# swarm_circuit.net
KiCad netlist of a schematic drawn in EAGLE
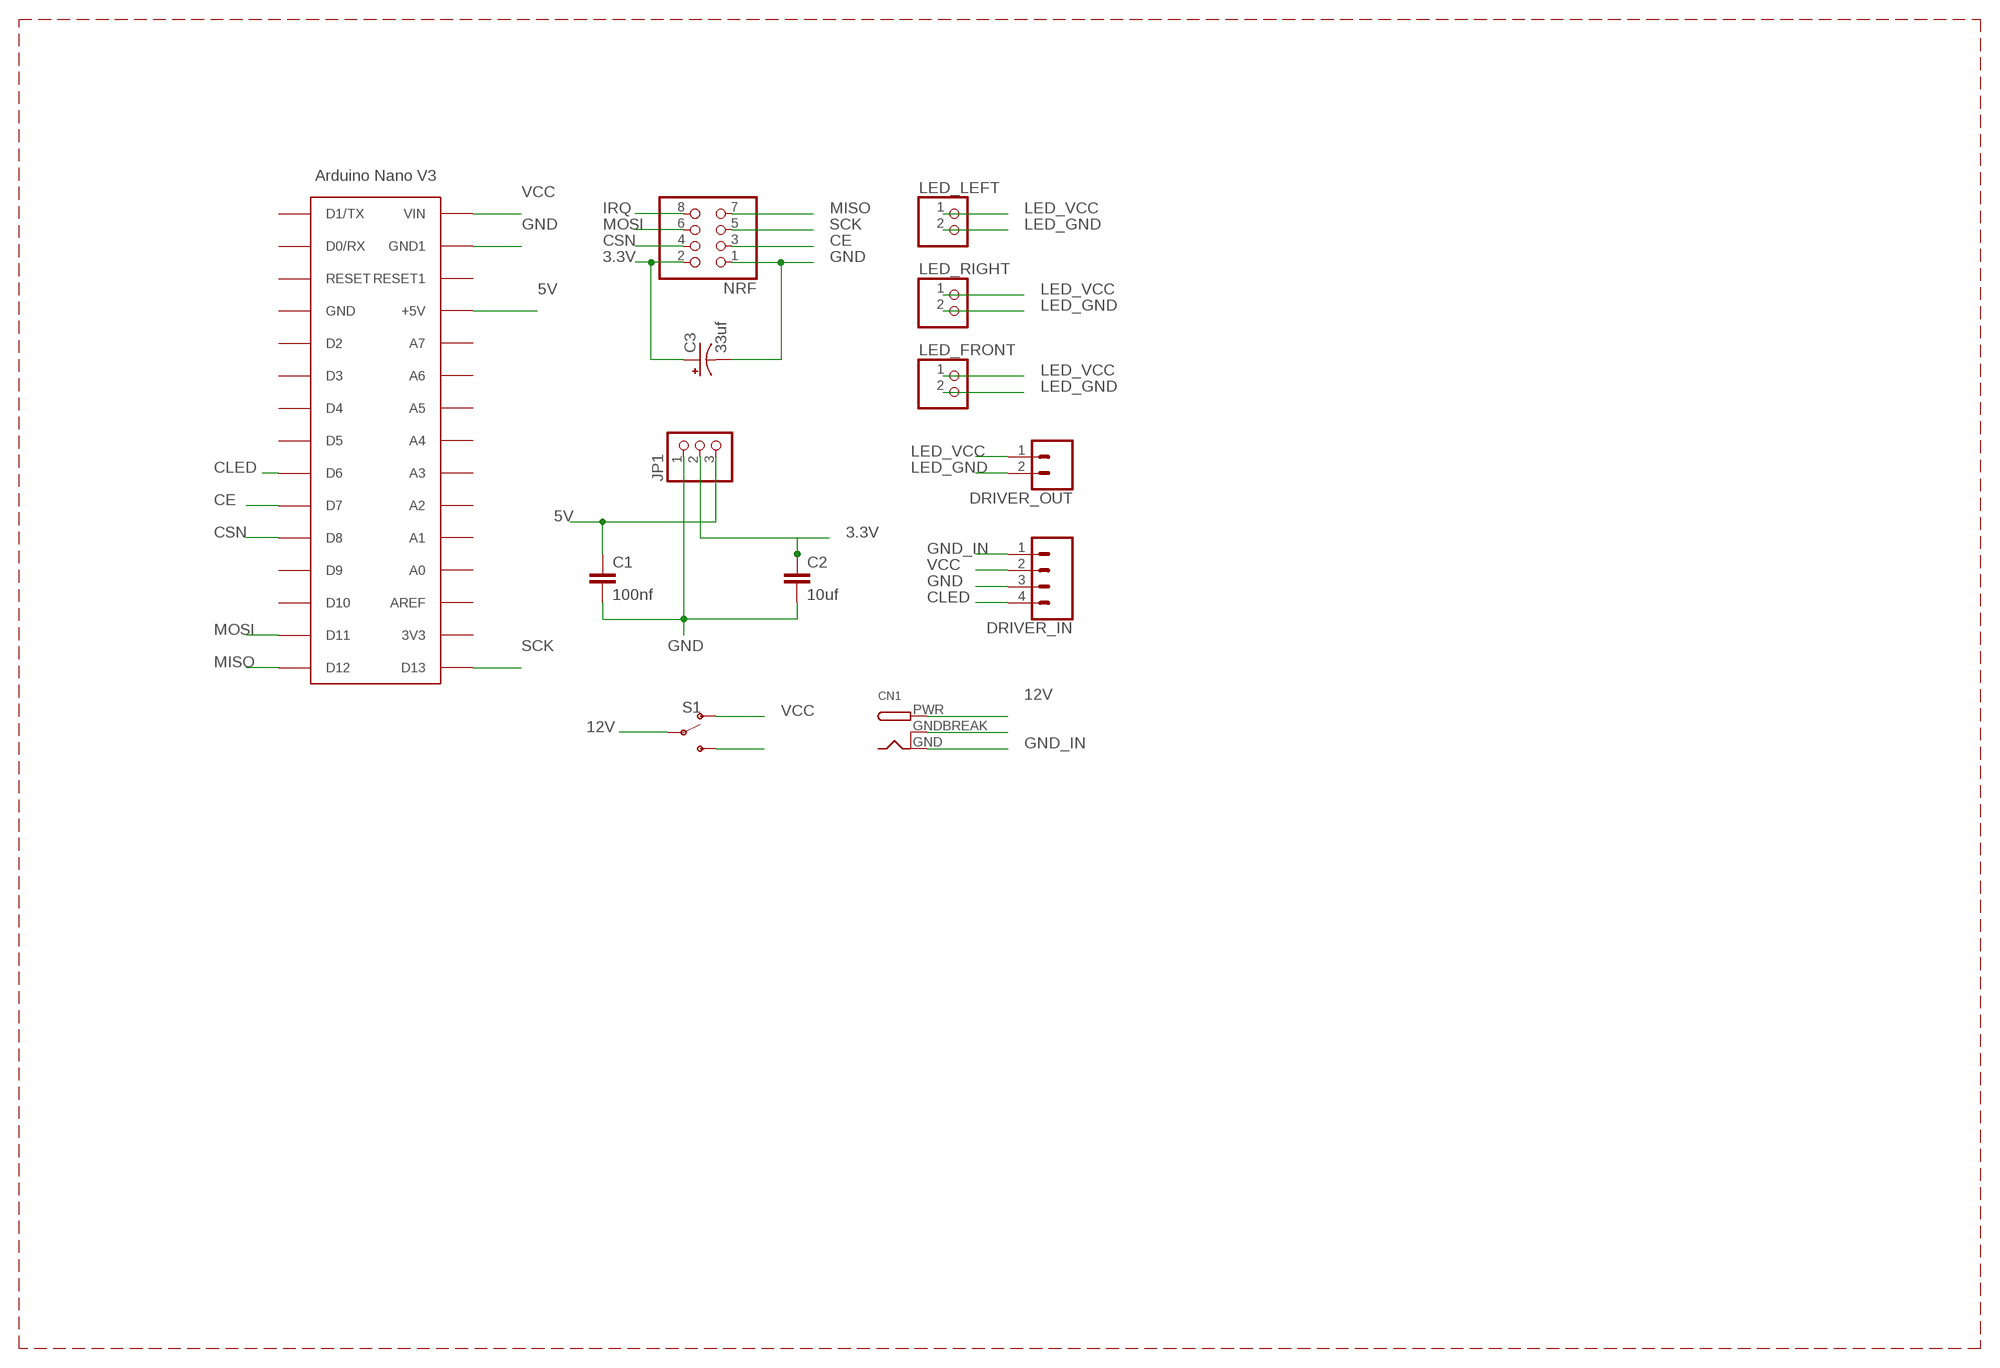
[diagram p0: schematic, sheet 1]

(export (version "E")
  (design (tool "Eeschema 10.0.6"))
  (components
    (comp (ref "C1")
      (value "100nf")
      (footprint "eagle-import:CAP-PTH-SMALL-KIT")
      (libsource (lib "eagle-import") (part "0.1UF-KIT-EZ-50V-20%"))
    )
    (comp (ref "C2")
      (value "10uf")
      (footprint "eagle-import:CAP-PTH-SMALL-KIT")
      (libsource (lib "eagle-import") (part "0.1UF-KIT-EZ-50V-20%"))
    )
    (comp (ref "C3")
      (value "33uf")
      (footprint "eagle-import:CPOL-RADIAL-5MM-10MM-KIT")
      (libsource (lib "eagle-import") (part "1000UF-RADIAL-5MM-35V-20%-KIT"))
    )
    (comp (ref "CN1")
      (value "DCBARRELPTH")
      (footprint "eagle-import:DCJACK_2MM_PTH")
      (libsource (lib "eagle-import") (part "DCBARRELPTH"))
    )
    (comp (ref "DRIVER_IN")
      (value "CONN_04")
      (footprint "eagle-import:1X04")
      (libsource (lib "eagle-import") (part "CONN_04"))
    )
    (comp (ref "DRIVER_OUT")
      (value "CONN_02")
      (footprint "eagle-import:1X02")
      (libsource (lib "eagle-import") (part "CONN_02"))
    )
    (comp (ref "JP1")
      (value "PINHD-1X3")
      (footprint "eagle-import:1X03")
      (libsource (lib "eagle-import") (part "PINHD-1X3"))
    )
    (comp (ref "LED_FRONT")
      (value "HEADER-1X2ROUND")
      (footprint "eagle-import:1X02_ROUND")
      (libsource (lib "eagle-import") (part "HEADER-1X2ROUND"))
    )
    (comp (ref "LED_LEFT")
      (value "HEADER-1X2ROUND")
      (footprint "eagle-import:1X02_ROUND")
      (libsource (lib "eagle-import") (part "HEADER-1X2ROUND"))
    )
    (comp (ref "LED_RIGHT")
      (value "HEADER-1X2ROUND")
      (footprint "eagle-import:1X02_ROUND")
      (libsource (lib "eagle-import") (part "HEADER-1X2ROUND"))
    )
    (comp (ref "NRF")
      (value "PINHD-2X4")
      (footprint "eagle-import:2X04")
      (libsource (lib "eagle-import") (part "PINHD-2X4"))
    )
    (comp (ref "S1")
      (value "SWITCH-SPDT-PTH-11.6X4.0MM")
      (footprint "eagle-import:SWITCH_SPDT_PTH_11.6X4.0MM")
      (libsource (lib "eagle-import") (part "SWITCH-SPDT-PTH-11.6X4.0MM"))
    )
    (comp (ref "U$1")
      (value "ARDUINONANO")
      (footprint "eagle-import:PDIP-32")
      (libsource (lib "eagle-import") (part "ARDUINONANO"))
    )
  )
  (nets
    (net (code "1") (name "/3.3V") (class "Default")
      (node (ref "C2") (pin "1") (pinfunction "1_1") (pintype "passive"))
      (node (ref "C3") (pin "+") (pinfunction "+_+") (pintype "passive"))
      (node (ref "JP1") (pin "2") (pinfunction "2_2") (pintype "passive"))
      (node (ref "NRF") (pin "2") (pinfunction "2_2") (pintype "passive"))
    )
    (net (code "2") (name "/5V") (class "Default")
      (node (ref "C1") (pin "1") (pinfunction "1_1") (pintype "passive"))
      (node (ref "JP1") (pin "3") (pinfunction "3_3") (pintype "passive"))
      (node (ref "U$1") (pin "+5V") (pinfunction "+5V_+5V") (pintype "bidirectional"))
    )
    (net (code "3") (name "/12V") (class "Default")
      (node (ref "CN1") (pin "PWR") (pinfunction "PWR_PWR") (pintype "power_in"))
      (node (ref "S1") (pin "2") (pinfunction "P_2") (pintype "passive"))
    )
    (net (code "4") (name "/CE") (class "Default")
      (node (ref "NRF") (pin "3") (pinfunction "3_3") (pintype "passive"))
      (node (ref "U$1") (pin "D7") (pinfunction "D7_D7") (pintype "bidirectional"))
    )
    (net (code "5") (name "/CLED") (class "Default")
      (node (ref "DRIVER_IN") (pin "4") (pinfunction "4_4") (pintype "passive"))
      (node (ref "U$1") (pin "D6") (pinfunction "D6_D6") (pintype "bidirectional"))
    )
    (net (code "6") (name "/CSN") (class "Default")
      (node (ref "NRF") (pin "4") (pinfunction "4_4") (pintype "passive"))
      (node (ref "U$1") (pin "D8") (pinfunction "D8_D8") (pintype "bidirectional"))
    )
    (net (code "7") (name "/GND") (class "Default")
      (node (ref "C1") (pin "2") (pinfunction "2_2") (pintype "passive"))
      (node (ref "C2") (pin "2") (pinfunction "2_2") (pintype "passive"))
      (node (ref "C3") (pin "-") (pinfunction "-_-") (pintype "passive"))
      (node (ref "DRIVER_IN") (pin "3") (pinfunction "3_3") (pintype "passive"))
      (node (ref "JP1") (pin "1") (pinfunction "1_1") (pintype "passive"))
      (node (ref "NRF") (pin "1") (pinfunction "1_1") (pintype "passive"))
      (node (ref "U$1") (pin "GND1") (pinfunction "GND1_GND1") (pintype "bidirectional"))
    )
    (net (code "8") (name "/GND_IN") (class "Default")
      (node (ref "CN1") (pin "GND") (pinfunction "GND_GND") (pintype "power_in"))
      (node (ref "DRIVER_IN") (pin "1") (pinfunction "1_1") (pintype "passive"))
    )
    (net (code "9") (name "/IRQ") (class "Default")
      (node (ref "NRF") (pin "8") (pinfunction "8_8") (pintype "passive"))
    )
    (net (code "10") (name "/LED_GND") (class "Default")
      (node (ref "DRIVER_OUT") (pin "2") (pinfunction "2_2") (pintype "passive"))
      (node (ref "LED_FRONT") (pin "2") (pinfunction "2_2") (pintype "passive"))
      (node (ref "LED_LEFT") (pin "2") (pinfunction "2_2") (pintype "passive"))
      (node (ref "LED_RIGHT") (pin "2") (pinfunction "2_2") (pintype "passive"))
    )
    (net (code "11") (name "/LED_VCC") (class "Default")
      (node (ref "DRIVER_OUT") (pin "1") (pinfunction "1_1") (pintype "passive"))
      (node (ref "LED_FRONT") (pin "1") (pinfunction "1_1") (pintype "passive"))
      (node (ref "LED_LEFT") (pin "1") (pinfunction "1_1") (pintype "passive"))
      (node (ref "LED_RIGHT") (pin "1") (pinfunction "1_1") (pintype "passive"))
    )
    (net (code "12") (name "/MISO") (class "Default")
      (node (ref "NRF") (pin "7") (pinfunction "7_7") (pintype "passive"))
      (node (ref "U$1") (pin "D12") (pinfunction "D12_D12") (pintype "bidirectional"))
    )
    (net (code "13") (name "/MOSI") (class "Default")
      (node (ref "NRF") (pin "6") (pinfunction "6_6") (pintype "passive"))
      (node (ref "U$1") (pin "D11") (pinfunction "D11_D11") (pintype "bidirectional"))
    )
    (net (code "14") (name "/SCK") (class "Default")
      (node (ref "NRF") (pin "5") (pinfunction "5_5") (pintype "passive"))
      (node (ref "U$1") (pin "D13") (pinfunction "D13_D13") (pintype "bidirectional"))
    )
    (net (code "15") (name "/VCC") (class "Default")
      (node (ref "DRIVER_IN") (pin "2") (pinfunction "2_2") (pintype "passive"))
      (node (ref "S1") (pin "1") (pinfunction "O_1") (pintype "passive"))
      (node (ref "S1") (pin "3") (pinfunction "S_3") (pintype "passive"))
      (node (ref "U$1") (pin "VIN") (pinfunction "VIN_VIN") (pintype "bidirectional"))
    )
    (net (code "16") (name "unconnected-(CN1-PadGNDBREAK)") (class "Default")
      (node (ref "CN1") (pin "GNDBREAK") (pinfunction "GNDBREAK_GNDBREAK") (pintype "power_in"))
    )
    (net (code "17") (name "unconnected-(U$1-A0-PadA7)") (class "Default")
      (node (ref "U$1") (pin "A7") (pinfunction "A0_A7") (pintype "bidirectional"))
    )
    (net (code "18") (name "unconnected-(U$1-A1-PadA6)") (class "Default")
      (node (ref "U$1") (pin "A6") (pinfunction "A1_A6") (pintype "bidirectional"))
    )
    (net (code "19") (name "unconnected-(U$1-A2-PadA5)") (class "Default")
      (node (ref "U$1") (pin "A5") (pinfunction "A2_A5") (pintype "bidirectional"))
    )
    (net (code "20") (name "unconnected-(U$1-A3-PadA4)") (class "Default")
      (node (ref "U$1") (pin "A4") (pinfunction "A3_A4") (pintype "bidirectional"))
    )
    (net (code "21") (name "unconnected-(U$1-A4-PadA3)") (class "Default")
      (node (ref "U$1") (pin "A3") (pinfunction "A4_A3") (pintype "bidirectional"))
    )
    (net (code "22") (name "unconnected-(U$1-A5-PadA2)") (class "Default")
      (node (ref "U$1") (pin "A2") (pinfunction "A5_A2") (pintype "bidirectional"))
    )
    (net (code "23") (name "unconnected-(U$1-A6-PadA1)") (class "Default")
      (node (ref "U$1") (pin "A1") (pinfunction "A6_A1") (pintype "bidirectional"))
    )
    (net (code "24") (name "unconnected-(U$1-A7-PadA0)") (class "Default")
      (node (ref "U$1") (pin "A0") (pinfunction "A7_A0") (pintype "bidirectional"))
    )
    (net (code "25") (name "unconnected-(U$1-Pad3V3)") (class "Default")
      (node (ref "U$1") (pin "3V3") (pinfunction "3V3_3V3") (pintype "bidirectional"))
    )
    (net (code "26") (name "unconnected-(U$1-PadAREF)") (class "Default")
      (node (ref "U$1") (pin "AREF") (pinfunction "AREF_AREF") (pintype "bidirectional"))
    )
    (net (code "27") (name "unconnected-(U$1-PadD0{slash}RX)") (class "Default")
      (node (ref "U$1") (pin "D0/RX") (pinfunction "D0/RX_D0/RX") (pintype "bidirectional"))
    )
    (net (code "28") (name "unconnected-(U$1-PadD1{slash}TX)") (class "Default")
      (node (ref "U$1") (pin "D1/TX") (pinfunction "D1/TX_D1/TX") (pintype "bidirectional"))
    )
    (net (code "29") (name "unconnected-(U$1-PadD2)") (class "Default")
      (node (ref "U$1") (pin "D2") (pinfunction "D2_D2") (pintype "bidirectional"))
    )
    (net (code "30") (name "unconnected-(U$1-PadD3)") (class "Default")
      (node (ref "U$1") (pin "D3") (pinfunction "D3_D3") (pintype "bidirectional"))
    )
    (net (code "31") (name "unconnected-(U$1-PadD4)") (class "Default")
      (node (ref "U$1") (pin "D4") (pinfunction "D4_D4") (pintype "bidirectional"))
    )
    (net (code "32") (name "unconnected-(U$1-PadD5)") (class "Default")
      (node (ref "U$1") (pin "D5") (pinfunction "D5_D5") (pintype "bidirectional"))
    )
    (net (code "33") (name "unconnected-(U$1-PadD9)") (class "Default")
      (node (ref "U$1") (pin "D9") (pinfunction "D9_D9") (pintype "bidirectional"))
    )
    (net (code "34") (name "unconnected-(U$1-PadD10)") (class "Default")
      (node (ref "U$1") (pin "D10") (pinfunction "D10_D10") (pintype "bidirectional"))
    )
    (net (code "35") (name "unconnected-(U$1-PadGND)") (class "Default")
      (node (ref "U$1") (pin "GND") (pinfunction "GND_GND") (pintype "bidirectional"))
    )
    (net (code "36") (name "unconnected-(U$1-PadRESET)") (class "Default")
      (node (ref "U$1") (pin "RESET") (pinfunction "RESET_RESET") (pintype "bidirectional"))
    )
    (net (code "37") (name "unconnected-(U$1-PadRESET1)") (class "Default")
      (node (ref "U$1") (pin "RESET1") (pinfunction "RESET1_RESET1") (pintype "bidirectional"))
    )
  )
)
